# YOTSUBA_GNSS-receiver_MAX_ver_1_5.net
KiCad netlist of a schematic drawn in EAGLE
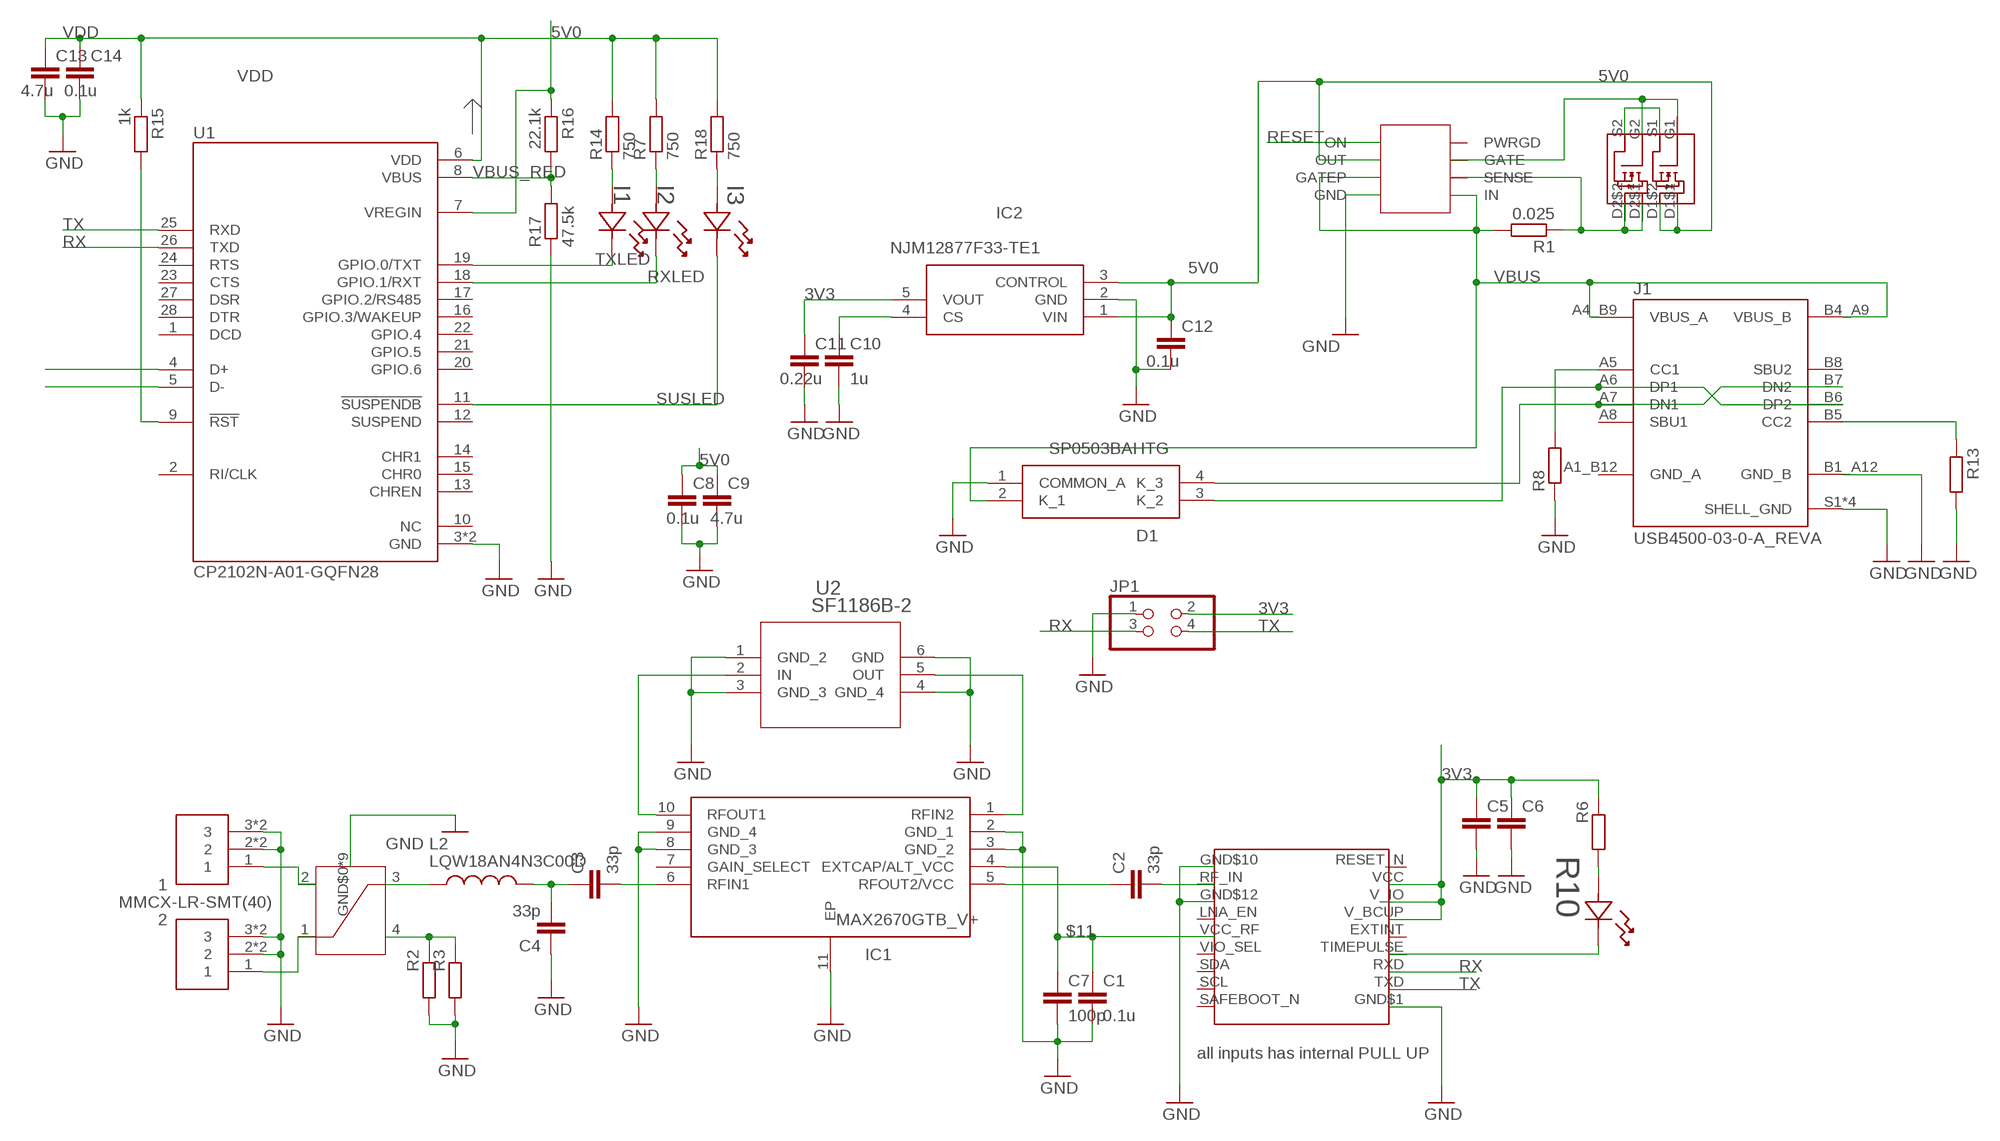
[diagram p0: schematic, sheet 1]

(export (version "E")
  (design (tool "Eeschema 10.0.6"))
  (components
    (comp (ref "1")
      (value "MMCX-LR-SMT(40)")
      (footprint "eagle-import:MMCX-LR-SMT(40)")
      (libsource (lib "eagle-import") (part "MMCX-LR-SMT(40)"))
    )
    (comp (ref "2")
      (value "MMCX-LR-SMT(40)")
      (footprint "eagle-import:MMCX-LR-SMT(40)")
      (libsource (lib "eagle-import") (part "MMCX-LR-SMT(40)"))
    )
    (comp (ref "C1")
      (value "0.1u")
      (footprint "eagle-import:C1608")
      (libsource (lib "eagle-import") (part "C-EUC1608"))
    )
    (comp (ref "C2")
      (value "33p")
      (footprint "eagle-import:C1608")
      (libsource (lib "eagle-import") (part "C-EUC1608"))
    )
    (comp (ref "C3")
      (value "33p")
      (footprint "eagle-import:C1608")
      (libsource (lib "eagle-import") (part "C-EUC1608"))
    )
    (comp (ref "C4")
      (value "33p")
      (footprint "eagle-import:C1608")
      (libsource (lib "eagle-import") (part "C-EUC1608"))
    )
    (comp (ref "C5")
      (value "C-EUC1608")
      (footprint "eagle-import:C1608")
      (libsource (lib "eagle-import") (part "C-EUC1608"))
    )
    (comp (ref "C6")
      (value "C-EUC1608")
      (footprint "eagle-import:C1608")
      (libsource (lib "eagle-import") (part "C-EUC1608"))
    )
    (comp (ref "C7")
      (value "100p")
      (footprint "eagle-import:C1608")
      (libsource (lib "eagle-import") (part "C-EUC1608"))
    )
    (comp (ref "C8")
      (value "0.1u")
      (footprint "eagle-import:C1608")
      (libsource (lib "eagle-import") (part "C-EUC1608"))
    )
    (comp (ref "C9")
      (value "4.7u")
      (footprint "eagle-import:C1608")
      (libsource (lib "eagle-import") (part "C-EUC1608"))
    )
    (comp (ref "C10")
      (value "1u")
      (footprint "eagle-import:C1608")
      (libsource (lib "eagle-import") (part "C-EUC1608"))
    )
    (comp (ref "C11")
      (value "0.22u")
      (footprint "eagle-import:C1608")
      (libsource (lib "eagle-import") (part "C-EUC1608"))
    )
    (comp (ref "C12")
      (value "0.1u")
      (footprint "eagle-import:C1608")
      (libsource (lib "eagle-import") (part "C-EUC1608"))
    )
    (comp (ref "C13")
      (value "4.7u")
      (footprint "eagle-import:C1608")
      (libsource (lib "eagle-import") (part "C-EUC1608"))
    )
    (comp (ref "C14")
      (value "0.1u")
      (footprint "eagle-import:C1608")
      (libsource (lib "eagle-import") (part "C-EUC1608"))
    )
    (comp (ref "D1")
      (value "SP0503BAHTG")
      (footprint "eagle-import:SP0503BAHTG")
      (fields (field (name "MOUSER_PART_NUMBER") "576-SP0503BAHTG"))
      (libsource (lib "eagle-import") (part "SP0503BAHTG"))
    )
    (comp (ref "I1")
      (value "SML-E12P8WT86")
      (footprint "eagle-import:LED_SMLD12_ROM")
      (fields (field (name "COPYRIGHT") "Copyright (C) 2023 Ultra Librarian. All rights reserved."))
      (libsource (lib "eagle-import") (part "SML-E12P8WT86"))
    )
    (comp (ref "I2")
      (value "SML-E12P8WT86")
      (footprint "eagle-import:LED_SMLD12_ROM")
      (fields (field (name "COPYRIGHT") "Copyright (C) 2023 Ultra Librarian. All rights reserved."))
      (libsource (lib "eagle-import") (part "SML-E12P8WT86"))
    )
    (comp (ref "I3")
      (value "SML-E12P8WT86")
      (footprint "eagle-import:LED_SMLD12_ROM")
      (fields (field (name "COPYRIGHT") "Copyright (C) 2023 Ultra Librarian. All rights reserved."))
      (libsource (lib "eagle-import") (part "SML-E12P8WT86"))
    )
    (comp (ref "IC1")
      (value "MAX2670GTB_V+")
      (footprint "eagle-import:SON50P300X300X80-11N")
      (fields
        (field (name "MANUFACTURER_PART_NUMBER") "MAX2670GTB/V+")
        (field (name "MOUSER_PART_NUMBER") "700-MAX2670GTB/V+")
      )
      (libsource (lib "eagle-import") (part "MAX2670GTB_V+"))
    )
    (comp (ref "IC2")
      (value "NJM12877F33-TE1")
      (footprint "eagle-import:SOT95P280X120-5N")
      (fields (field (name "MOUSER_PART_NUMBER") "513-NJM12877F33-TE1"))
      (libsource (lib "eagle-import") (part "NJM12877F33-TE1"))
    )
    (comp (ref "J1")
      (value "USB4500-03-0-A_REVA")
      (footprint "eagle-import:GCT_USB4500-03-0-A_REVA")
      (fields
        (field (name "DIGI-KEY_PART_NUMBER") "2073-USB4500-03-0-ATR-ND")
        (field (name "MF") "Global Connector Technology")
        (field (name "MP") "USB4500-03-0-A")
      )
      (libsource (lib "eagle-import") (part "USB4500-03-0-A_REVA"))
    )
    (comp (ref "JP1")
      (value "PINHD-2X2")
      (footprint "eagle-import:2X02")
      (libsource (lib "eagle-import") (part "PINHD-2X2"))
    )
    (comp (ref "L2")
      (value "LQW18AN4N3C00D")
      (footprint "eagle-import:INDC1608X100N")
      (fields (field (name "DIGIKEY_PART_NUMBER") "490-6896-2-ND") (field (name "MF") "Murata"))
      (libsource (lib "eagle-import") (part "LQW18AN4N3C00D"))
    )
    (comp (ref "R1")
      (value "0.025")
      (footprint "eagle-import:R0603")
      (libsource (lib "eagle-import") (part "R-EU_R0603"))
    )
    (comp (ref "R2")
      (value "R-EU_R0603")
      (footprint "eagle-import:R0603")
      (libsource (lib "eagle-import") (part "R-EU_R0603"))
    )
    (comp (ref "R3")
      (value "R-EU_R0603")
      (footprint "eagle-import:R0603")
      (libsource (lib "eagle-import") (part "R-EU_R0603"))
    )
    (comp (ref "R6")
      (value "R-EU_R0603")
      (footprint "eagle-import:R0603")
      (libsource (lib "eagle-import") (part "R-EU_R0603"))
    )
    (comp (ref "R7")
      (value "750")
      (footprint "eagle-import:R0603")
      (libsource (lib "eagle-import") (part "R-EU_R0603"))
    )
    (comp (ref "R8")
      (value "R-EU_R0603")
      (footprint "eagle-import:R0603")
      (libsource (lib "eagle-import") (part "R-EU_R0603"))
    )
    (comp (ref "R10")
      (value "SML-E12P8WT86")
      (footprint "eagle-import:LED_SMLD12_ROM")
      (fields (field (name "COPYRIGHT") "Copyright (C) 2023 Ultra Librarian. All rights reserved."))
      (libsource (lib "eagle-import") (part "SML-E12P8WT86"))
    )
    (comp (ref "R13")
      (value "R-EU_R0603")
      (footprint "eagle-import:R0603")
      (libsource (lib "eagle-import") (part "R-EU_R0603"))
    )
    (comp (ref "R14")
      (value "750")
      (footprint "eagle-import:R0603")
      (libsource (lib "eagle-import") (part "R-EU_R0603"))
    )
    (comp (ref "R15")
      (value "1k")
      (footprint "eagle-import:R0603")
      (libsource (lib "eagle-import") (part "R-EU_R0603"))
    )
    (comp (ref "R16")
      (value "22.1k")
      (footprint "eagle-import:R0603")
      (libsource (lib "eagle-import") (part "R-EU_R0603"))
    )
    (comp (ref "R17")
      (value "47.5k")
      (footprint "eagle-import:R0603")
      (libsource (lib "eagle-import") (part "R-EU_R0603"))
    )
    (comp (ref "R18")
      (value "750")
      (footprint "eagle-import:R0603")
      (libsource (lib "eagle-import") (part "R-EU_R0603"))
    )
    (comp (ref "U$1")
      (value "MAX_M10S")
      (footprint "eagle-import:MAX-M10S")
      (libsource (lib "eagle-import") (part "MAX_M10S"))
    )
    (comp (ref "U$3")
      (value "HC125.A")
      (footprint "eagle-import:HC125.A")
      (libsource (lib "eagle-import") (part "HC125.A"))
    )
    (comp (ref "U$7")
      (value "DMG6898LSD")
      (footprint "eagle-import:SOIC127P600X150-8N")
      (libsource (lib "eagle-import") (part "DMG6898LSD"))
    )
    (comp (ref "U$8")
      (value "LTC4361")
      (footprint "eagle-import:SOP65P280X100-8N")
      (libsource (lib "eagle-import") (part "LTC4361"))
    )
    (comp (ref "U1")
      (value "CP2102N-A01-GQFN28")
      (footprint "eagle-import:QFN50P500X500X80-29N")
      (fields (field (name "MF") "Silicon Labs"))
      (libsource (lib "eagle-import") (part "CP2102N-A01-GQFN28"))
    )
    (comp (ref "U2")
      (value "SF1186B-2")
      (footprint "eagle-import:SM3030_MUR")
      (fields (field (name "COPYRIGHT") "Copyright (C) 2023 Ultra Librarian. All rights reserved."))
      (libsource (lib "eagle-import") (part "SF1186B-2"))
    )
  )
  (nets
    (net (code "1") (name "/$11") (class "Default")
      (node (ref "C1") (pin "1") (pinfunction "1_1") (pintype "passive"))
      (node (ref "C7") (pin "1") (pinfunction "1_1") (pintype "passive"))
      (node (ref "IC1") (pin "4") (pinfunction "EXTCAP/ALT_VCC_4") (pintype "bidirectional"))
      (node (ref "U$1") (pin "VCC_RF") (pinfunction "VCC_RF_VCC_RF") (pintype "bidirectional"))
    )
    (net (code "2") (name "/3V3") (class "Default")
      (node (ref "C11") (pin "1") (pinfunction "1_1") (pintype "passive"))
      (node (ref "C5") (pin "1") (pinfunction "1_1") (pintype "passive"))
      (node (ref "C6") (pin "1") (pinfunction "1_1") (pintype "passive"))
      (node (ref "IC2") (pin "5") (pinfunction "VOUT_5") (pintype "bidirectional"))
      (node (ref "JP1") (pin "2") (pinfunction "2_2") (pintype "passive"))
      (node (ref "R6") (pin "2") (pinfunction "2_2") (pintype "passive"))
      (node (ref "U$1") (pin "VCC") (pinfunction "VCC_VCC") (pintype "bidirectional"))
      (node (ref "U$1") (pin "V_BCUP") (pinfunction "V_BCKP_V_BCUP") (pintype "bidirectional"))
      (node (ref "U$1") (pin "V_IO") (pinfunction "V_IO_V_IO") (pintype "bidirectional"))
    )
    (net (code "3") (name "/5V0") (class "Default")
      (node (ref "C12") (pin "1") (pinfunction "1_1") (pintype "passive"))
      (node (ref "C8") (pin "1") (pinfunction "1_1") (pintype "passive"))
      (node (ref "C9") (pin "1") (pinfunction "1_1") (pintype "passive"))
      (node (ref "IC2") (pin "1") (pinfunction "VIN_1") (pintype "bidirectional"))
      (node (ref "IC2") (pin "3") (pinfunction "CONTROL_3") (pintype "bidirectional"))
      (node (ref "R16") (pin "1") (pinfunction "1_1") (pintype "passive"))
      (node (ref "U$7") (pin "D1$1") (pinfunction "D1$1_D1$1") (pintype "bidirectional"))
      (node (ref "U$7") (pin "D1$2") (pinfunction "D1$2_D1$2") (pintype "bidirectional"))
      (node (ref "U$8") (pin "OUT") (pinfunction "OUT_OUT") (pintype "bidirectional"))
      (node (ref "U1") (pin "7") (pinfunction "VREGIN_7") (pintype "power_in"))
    )
    (net (code "4") (name "/D+") (class "Default")
      (node (ref "D1") (pin "3") (pinfunction "K_2_3") (pintype "bidirectional"))
      (node (ref "J1") (pin "A6") (pinfunction "DP1_A6") (pintype "bidirectional"))
      (node (ref "J1") (pin "B6") (pinfunction "DP2_B6") (pintype "bidirectional"))
      (node (ref "U1") (pin "4") (pinfunction "D+_4") (pintype "bidirectional"))
    )
    (net (code "5") (name "/D-") (class "Default")
      (node (ref "D1") (pin "4") (pinfunction "K_3_4") (pintype "bidirectional"))
      (node (ref "J1") (pin "A7") (pinfunction "DN1_A7") (pintype "bidirectional"))
      (node (ref "J1") (pin "B7") (pinfunction "DN2_B7") (pintype "bidirectional"))
      (node (ref "U1") (pin "5") (pinfunction "D-_5") (pintype "bidirectional"))
    )
    (net (code "6") (name "/GND_A") (class "Default")
      (node (ref "J1") (pin "A1_B12") (pinfunction "GND_A_A1_B12") (pintype "power_in"))
    )
    (net (code "7") (name "/RESET") (class "Default")
      (node (ref "U$8") (pin "ON") (pinfunction "ON_ON") (pintype "bidirectional"))
    )
    (net (code "8") (name "/RX") (class "Default")
      (node (ref "JP1") (pin "3") (pinfunction "3_3") (pintype "passive"))
      (node (ref "U$1") (pin "RXD") (pinfunction "RXD_RXD") (pintype "bidirectional"))
      (node (ref "U1") (pin "26") (pinfunction "TXD_26") (pintype "output"))
    )
    (net (code "9") (name "/RXLED") (class "Default")
      (node (ref "I2") (pin "1") (pinfunction "1_1") (pintype "passive"))
      (node (ref "U1") (pin "18") (pinfunction "GPIO.1/RXT_18") (pintype "bidirectional"))
    )
    (net (code "10") (name "/SUSLED") (class "Default")
      (node (ref "I3") (pin "1") (pinfunction "1_1") (pintype "passive"))
      (node (ref "U1") (pin "11") (pinfunction "~{SUSPENDB}_11") (pintype "output"))
    )
    (net (code "11") (name "/TX") (class "Default")
      (node (ref "JP1") (pin "4") (pinfunction "4_4") (pintype "passive"))
      (node (ref "U$1") (pin "TXD") (pinfunction "TXD_TXD") (pintype "bidirectional"))
      (node (ref "U1") (pin "25") (pinfunction "RXD_25") (pintype "input"))
    )
    (net (code "12") (name "/TXLED") (class "Default")
      (node (ref "I1") (pin "1") (pinfunction "1_1") (pintype "passive"))
      (node (ref "U1") (pin "19") (pinfunction "GPIO.0/TXT_19") (pintype "bidirectional"))
    )
    (net (code "13") (name "/VBUS") (class "Default")
      (node (ref "D1") (pin "2") (pinfunction "K_1_2") (pintype "bidirectional"))
      (node (ref "J1") (pin "A4_B9") (pinfunction "VBUS_A_A4_B9") (pintype "power_in"))
      (node (ref "J1") (pin "B4_A9") (pinfunction "VBUS_B_B4_A9") (pintype "power_in"))
      (node (ref "R1") (pin "2") (pinfunction "2_2") (pintype "passive"))
      (node (ref "U$8") (pin "GATEP") (pinfunction "GATEP_GATEP") (pintype "bidirectional"))
      (node (ref "U$8") (pin "IN") (pinfunction "IN_IN") (pintype "bidirectional"))
    )
    (net (code "14") (name "/VBUS_RED") (class "Default")
      (node (ref "R16") (pin "2") (pinfunction "2_2") (pintype "passive"))
      (node (ref "R17") (pin "2") (pinfunction "2_2") (pintype "passive"))
      (node (ref "U1") (pin "8") (pinfunction "VBUS_8") (pintype "power_in"))
    )
    (net (code "15") (name "/VDD") (class "Default")
      (node (ref "C13") (pin "1") (pinfunction "1_1") (pintype "passive"))
      (node (ref "C14") (pin "1") (pinfunction "1_1") (pintype "passive"))
      (node (ref "R14") (pin "2") (pinfunction "2_2") (pintype "passive"))
      (node (ref "R15") (pin "1") (pinfunction "1_1") (pintype "passive"))
      (node (ref "R18") (pin "2") (pinfunction "2_2") (pintype "passive"))
      (node (ref "R7") (pin "2") (pinfunction "2_2") (pintype "passive"))
      (node (ref "U1") (pin "6") (pinfunction "VDD_6") (pintype "power_in"))
    )
    (net (code "16") (name "GND") (class "Default")
      (node (ref "1") (pin "2") (pinfunction "2_2") (pintype "bidirectional"))
      (node (ref "1") (pin "3") (pinfunction "3_3") (pintype "bidirectional"))
      (node (ref "1") (pin "4") (pinfunction "2_4") (pintype "bidirectional"))
      (node (ref "1") (pin "5") (pinfunction "3_5") (pintype "bidirectional"))
      (node (ref "2") (pin "2") (pinfunction "2_2") (pintype "bidirectional"))
      (node (ref "2") (pin "3") (pinfunction "3_3") (pintype "bidirectional"))
      (node (ref "2") (pin "4") (pinfunction "2_4") (pintype "bidirectional"))
      (node (ref "2") (pin "5") (pinfunction "3_5") (pintype "bidirectional"))
      (node (ref "C1") (pin "2") (pinfunction "2_2") (pintype "passive"))
      (node (ref "C10") (pin "2") (pinfunction "2_2") (pintype "passive"))
      (node (ref "C11") (pin "2") (pinfunction "2_2") (pintype "passive"))
      (node (ref "C12") (pin "2") (pinfunction "2_2") (pintype "passive"))
      (node (ref "C13") (pin "2") (pinfunction "2_2") (pintype "passive"))
      (node (ref "C14") (pin "2") (pinfunction "2_2") (pintype "passive"))
      (node (ref "C4") (pin "1") (pinfunction "1_1") (pintype "passive"))
      (node (ref "C5") (pin "2") (pinfunction "2_2") (pintype "passive"))
      (node (ref "C6") (pin "2") (pinfunction "2_2") (pintype "passive"))
      (node (ref "C7") (pin "2") (pinfunction "2_2") (pintype "passive"))
      (node (ref "C8") (pin "2") (pinfunction "2_2") (pintype "passive"))
      (node (ref "C9") (pin "2") (pinfunction "2_2") (pintype "passive"))
      (node (ref "D1") (pin "1") (pinfunction "COMMON_A_1") (pintype "bidirectional"))
      (node (ref "IC1") (pin "11") (pinfunction "EP_11") (pintype "bidirectional"))
      (node (ref "IC1") (pin "2") (pinfunction "GND_1_2") (pintype "bidirectional"))
      (node (ref "IC1") (pin "3") (pinfunction "GND_2_3") (pintype "bidirectional"))
      (node (ref "IC1") (pin "8") (pinfunction "GND_3_8") (pintype "bidirectional"))
      (node (ref "IC1") (pin "9") (pinfunction "GND_4_9") (pintype "bidirectional"))
      (node (ref "IC2") (pin "2") (pinfunction "GND_2") (pintype "bidirectional"))
      (node (ref "J1") (pin "B1_A12") (pinfunction "GND_B_B1_A12") (pintype "power_in"))
      (node (ref "J1") (pin "S1") (pinfunction "SHELL_GND_S1") (pintype "power_in"))
      (node (ref "J1") (pin "S2") (pinfunction "SHELL_GND_S2") (pintype "power_in"))
      (node (ref "J1") (pin "S3") (pinfunction "SHELL_GND_S3") (pintype "power_in"))
      (node (ref "J1") (pin "S4") (pinfunction "SHELL_GND_S4") (pintype "power_in"))
      (node (ref "JP1") (pin "1") (pinfunction "1_1") (pintype "passive"))
      (node (ref "R13") (pin "2") (pinfunction "2_2") (pintype "passive"))
      (node (ref "R17") (pin "1") (pinfunction "1_1") (pintype "passive"))
      (node (ref "R2") (pin "1") (pinfunction "1_1") (pintype "passive"))
      (node (ref "R3") (pin "1") (pinfunction "1_1") (pintype "passive"))
      (node (ref "R8") (pin "1") (pinfunction "1_1") (pintype "passive"))
      (node (ref "U$1") (pin "GND$1") (pinfunction "GND$1_GND$1") (pintype "bidirectional"))
      (node (ref "U$1") (pin "GND$10") (pinfunction "GND$10_GND$10") (pintype "bidirectional"))
      (node (ref "U$1") (pin "GND$12") (pinfunction "GND$12_GND$12") (pintype "bidirectional"))
      (node (ref "U$3") (pin "GND$0") (pinfunction "GND_GND$0") (pintype "bidirectional"))
      (node (ref "U$3") (pin "GND$1") (pinfunction "GND_GND$1") (pintype "bidirectional"))
      (node (ref "U$3") (pin "GND$2") (pinfunction "GND_GND$2") (pintype "bidirectional"))
      (node (ref "U$3") (pin "GND$3") (pinfunction "GND_GND$3") (pintype "bidirectional"))
      (node (ref "U$3") (pin "GND$4") (pinfunction "GND_GND$4") (pintype "bidirectional"))
      (node (ref "U$3") (pin "GND$5") (pinfunction "GND_GND$5") (pintype "bidirectional"))
      (node (ref "U$3") (pin "GND$6") (pinfunction "GND_GND$6") (pintype "bidirectional"))
      (node (ref "U$3") (pin "GND$7") (pinfunction "GND_GND$7") (pintype "bidirectional"))
      (node (ref "U$3") (pin "GND$8") (pinfunction "GND_GND$8") (pintype "bidirectional"))
      (node (ref "U$8") (pin "GND") (pinfunction "GND_GND") (pintype "bidirectional"))
      (node (ref "U1") (pin "29") (pinfunction "GND_29") (pintype "power_in"))
      (node (ref "U1") (pin "3") (pinfunction "GND_3") (pintype "power_in"))
      (node (ref "U2") (pin "1") (pinfunction "GND_2_1") (pintype "passive"))
      (node (ref "U2") (pin "3") (pinfunction "GND_3_3") (pintype "passive"))
      (node (ref "U2") (pin "4") (pinfunction "GND_4_4") (pintype "passive"))
      (node (ref "U2") (pin "6") (pinfunction "GND_6") (pintype "passive"))
    )
    (net (code "17") (name "Net-(1-Pad1)") (class "Default")
      (node (ref "1") (pin "1") (pinfunction "1_1") (pintype "bidirectional"))
      (node (ref "U$3") (pin "2") (pinfunction "2_2") (pintype "bidirectional"))
    )
    (net (code "18") (name "Net-(2-Pad1)") (class "Default")
      (node (ref "2") (pin "1") (pinfunction "1_1") (pintype "bidirectional"))
      (node (ref "U$3") (pin "1") (pinfunction "1_1") (pintype "bidirectional"))
    )
    (net (code "19") (name "Net-(C2-Pad2)") (class "Default")
      (node (ref "C2") (pin "2") (pinfunction "2_2") (pintype "passive"))
      (node (ref "U$1") (pin "RF_IN") (pinfunction "RF_IN_RF_IN") (pintype "bidirectional"))
    )
    (net (code "20") (name "Net-(C3-Pad1)") (class "Default")
      (node (ref "C3") (pin "1") (pinfunction "1_1") (pintype "passive"))
      (node (ref "C4") (pin "2") (pinfunction "2_2") (pintype "passive"))
      (node (ref "L2") (pin "2") (pinfunction "2_2") (pintype "passive"))
    )
    (net (code "21") (name "Net-(I1-Pad2)") (class "Default")
      (node (ref "I1") (pin "2") (pinfunction "2_2") (pintype "passive"))
      (node (ref "R14") (pin "1") (pinfunction "1_1") (pintype "passive"))
    )
    (net (code "22") (name "Net-(I2-Pad2)") (class "Default")
      (node (ref "I2") (pin "2") (pinfunction "2_2") (pintype "passive"))
      (node (ref "R7") (pin "1") (pinfunction "1_1") (pintype "passive"))
    )
    (net (code "23") (name "Net-(I3-Pad2)") (class "Default")
      (node (ref "I3") (pin "2") (pinfunction "2_2") (pintype "passive"))
      (node (ref "R18") (pin "1") (pinfunction "1_1") (pintype "passive"))
    )
    (net (code "24") (name "Net-(IC1-RFIN1)") (class "Default")
      (node (ref "C3") (pin "2") (pinfunction "2_2") (pintype "passive"))
      (node (ref "IC1") (pin "6") (pinfunction "RFIN1_6") (pintype "bidirectional"))
    )
    (net (code "25") (name "Net-(IC1-RFIN2)") (class "Default")
      (node (ref "IC1") (pin "1") (pinfunction "RFIN2_1") (pintype "bidirectional"))
      (node (ref "U2") (pin "5") (pinfunction "OUT_5") (pintype "output"))
    )
    (net (code "26") (name "Net-(IC1-RFOUT1)") (class "Default")
      (node (ref "IC1") (pin "10") (pinfunction "RFOUT1_10") (pintype "bidirectional"))
      (node (ref "U2") (pin "2") (pinfunction "IN_2") (pintype "input"))
    )
    (net (code "27") (name "Net-(IC1-RFOUT2{slash}VCC)") (class "Default")
      (node (ref "C2") (pin "1") (pinfunction "1_1") (pintype "passive"))
      (node (ref "IC1") (pin "5") (pinfunction "RFOUT2/VCC_5") (pintype "bidirectional"))
    )
    (net (code "28") (name "Net-(IC2-CS)") (class "Default")
      (node (ref "C10") (pin "1") (pinfunction "1_1") (pintype "passive"))
      (node (ref "IC2") (pin "4") (pinfunction "CS_4") (pintype "bidirectional"))
    )
    (net (code "29") (name "Net-(J1-CC1)") (class "Default")
      (node (ref "J1") (pin "A5") (pinfunction "CC1_A5") (pintype "bidirectional"))
      (node (ref "R8") (pin "2") (pinfunction "2_2") (pintype "passive"))
    )
    (net (code "30") (name "Net-(J1-CC2)") (class "Default")
      (node (ref "J1") (pin "B5") (pinfunction "CC2_B5") (pintype "bidirectional"))
      (node (ref "R13") (pin "1") (pinfunction "1_1") (pintype "passive"))
    )
    (net (code "31") (name "Net-(L2-Pad1)") (class "Default")
      (node (ref "L2") (pin "1") (pinfunction "1_1") (pintype "passive"))
      (node (ref "U$3") (pin "3") (pinfunction "3_3") (pintype "bidirectional"))
    )
    (net (code "32") (name "Net-(R1-Pad1)") (class "Default")
      (node (ref "R1") (pin "1") (pinfunction "1_1") (pintype "passive"))
      (node (ref "U$7") (pin "D2$1") (pinfunction "D2$1_D2$1") (pintype "bidirectional"))
      (node (ref "U$7") (pin "D2$2") (pinfunction "D2$2_D2$2") (pintype "bidirectional"))
      (node (ref "U$8") (pin "SENSE") (pinfunction "SENSE_SENSE") (pintype "bidirectional"))
    )
    (net (code "33") (name "Net-(R2-Pad2)") (class "Default")
      (node (ref "R2") (pin "2") (pinfunction "2_2") (pintype "passive"))
      (node (ref "R3") (pin "2") (pinfunction "2_2") (pintype "passive"))
      (node (ref "U$3") (pin "4") (pinfunction "4_4") (pintype "bidirectional"))
    )
    (net (code "34") (name "Net-(R10-Pad1)") (class "Default")
      (node (ref "R10") (pin "1") (pinfunction "1_1") (pintype "passive"))
      (node (ref "U$1") (pin "TIMEPULSE") (pinfunction "TIMEPULSE_TIMEPULSE") (pintype "bidirectional"))
    )
    (net (code "35") (name "Net-(R10-Pad2)") (class "Default")
      (node (ref "R10") (pin "2") (pinfunction "2_2") (pintype "passive"))
      (node (ref "R6") (pin "1") (pinfunction "1_1") (pintype "passive"))
    )
    (net (code "36") (name "Net-(U$7-PadG1)") (class "Default")
      (node (ref "U$7") (pin "G1") (pinfunction "G1_G1") (pintype "bidirectional"))
      (node (ref "U$7") (pin "G2") (pinfunction "G2_G2") (pintype "bidirectional"))
      (node (ref "U$8") (pin "GATE") (pinfunction "GATE_GATE") (pintype "bidirectional"))
    )
    (net (code "37") (name "Net-(U$7-PadS1)") (class "Default")
      (node (ref "U$7") (pin "S1") (pinfunction "S1_S1") (pintype "bidirectional"))
      (node (ref "U$7") (pin "S2") (pinfunction "S2_S2") (pintype "bidirectional"))
    )
    (net (code "38") (name "Net-(U1-~{RST})") (class "Default")
      (node (ref "R15") (pin "2") (pinfunction "2_2") (pintype "passive"))
      (node (ref "U1") (pin "9") (pinfunction "~{RST}_9") (pintype "input"))
    )
    (net (code "39") (name "unconnected-(IC1-GAIN_SELECT-Pad7)") (class "Default")
      (node (ref "IC1") (pin "7") (pinfunction "GAIN_SELECT_7") (pintype "bidirectional"))
    )
    (net (code "40") (name "unconnected-(J1-SBU1-PadA8)") (class "Default")
      (node (ref "J1") (pin "A8") (pinfunction "SBU1_A8") (pintype "bidirectional"))
    )
    (net (code "41") (name "unconnected-(J1-SBU2-PadB8)") (class "Default")
      (node (ref "J1") (pin "B8") (pinfunction "SBU2_B8") (pintype "bidirectional"))
    )
    (net (code "42") (name "unconnected-(U$1-PadEXTINT)") (class "Default")
      (node (ref "U$1") (pin "EXTINT") (pinfunction "EXTINT_EXTINT") (pintype "bidirectional"))
    )
    (net (code "43") (name "unconnected-(U$1-PadLNA_EN)") (class "Default")
      (node (ref "U$1") (pin "LNA_EN") (pinfunction "LNA_EN_LNA_EN") (pintype "bidirectional"))
    )
    (net (code "44") (name "unconnected-(U$1-PadRESET_N)") (class "Default")
      (node (ref "U$1") (pin "RESET_N") (pinfunction "RESET_N_RESET_N") (pintype "bidirectional"))
    )
    (net (code "45") (name "unconnected-(U$1-PadSAFEBOOT_N)") (class "Default")
      (node (ref "U$1") (pin "SAFEBOOT_N") (pinfunction "SAFEBOOT_N_SAFEBOOT_N") (pintype "bidirectional"))
    )
    (net (code "46") (name "unconnected-(U$1-PadSCL)") (class "Default")
      (node (ref "U$1") (pin "SCL") (pinfunction "SCL_SCL") (pintype "bidirectional"))
    )
    (net (code "47") (name "unconnected-(U$1-PadSDA)") (class "Default")
      (node (ref "U$1") (pin "SDA") (pinfunction "SDA_SDA") (pintype "bidirectional"))
    )
    (net (code "48") (name "unconnected-(U$1-PadVIO_SEL)") (class "Default")
      (node (ref "U$1") (pin "VIO_SEL") (pinfunction "VIO_SEL_VIO_SEL") (pintype "bidirectional"))
    )
    (net (code "49") (name "unconnected-(U$8-PadPWRGD)") (class "Default")
      (node (ref "U$8") (pin "PWRGD") (pinfunction "PWRGD_PWRGD") (pintype "bidirectional"))
    )
    (net (code "50") (name "unconnected-(U1-CHR0-Pad15)") (class "Default")
      (node (ref "U1") (pin "15") (pinfunction "CHR0_15") (pintype "output"))
    )
    (net (code "51") (name "unconnected-(U1-CHR1-Pad14)") (class "Default")
      (node (ref "U1") (pin "14") (pinfunction "CHR1_14") (pintype "output"))
    )
    (net (code "52") (name "unconnected-(U1-CHREN-Pad13)") (class "Default")
      (node (ref "U1") (pin "13") (pinfunction "CHREN_13") (pintype "output"))
    )
    (net (code "53") (name "unconnected-(U1-CTS-Pad23)") (class "Default")
      (node (ref "U1") (pin "23") (pinfunction "CTS_23") (pintype "input"))
    )
    (net (code "54") (name "unconnected-(U1-DCD-Pad1)") (class "Default")
      (node (ref "U1") (pin "1") (pinfunction "DCD_1") (pintype "input"))
    )
    (net (code "55") (name "unconnected-(U1-DSR-Pad27)") (class "Default")
      (node (ref "U1") (pin "27") (pinfunction "DSR_27") (pintype "input"))
    )
    (net (code "56") (name "unconnected-(U1-DTR-Pad28)") (class "Default")
      (node (ref "U1") (pin "28") (pinfunction "DTR_28") (pintype "output"))
    )
    (net (code "57") (name "unconnected-(U1-GPIO.2{slash}RS485-Pad17)") (class "Default")
      (node (ref "U1") (pin "17") (pinfunction "GPIO.2/RS485_17") (pintype "bidirectional"))
    )
    (net (code "58") (name "unconnected-(U1-GPIO.3{slash}WAKEUP-Pad16)") (class "Default")
      (node (ref "U1") (pin "16") (pinfunction "GPIO.3/WAKEUP_16") (pintype "bidirectional"))
    )
    (net (code "59") (name "unconnected-(U1-GPIO.4-Pad22)") (class "Default")
      (node (ref "U1") (pin "22") (pinfunction "GPIO.4_22") (pintype "bidirectional"))
    )
    (net (code "60") (name "unconnected-(U1-GPIO.5-Pad21)") (class "Default")
      (node (ref "U1") (pin "21") (pinfunction "GPIO.5_21") (pintype "bidirectional"))
    )
    (net (code "61") (name "unconnected-(U1-GPIO.6-Pad20)") (class "Default")
      (node (ref "U1") (pin "20") (pinfunction "GPIO.6_20") (pintype "bidirectional"))
    )
    (net (code "62") (name "unconnected-(U1-NC-Pad10)") (class "Default")
      (node (ref "U1") (pin "10") (pinfunction "NC_10") (pintype "no_connect"))
    )
    (net (code "63") (name "unconnected-(U1-RI{slash}CLK-Pad2)") (class "Default")
      (node (ref "U1") (pin "2") (pinfunction "RI/CLK_2") (pintype "bidirectional"))
    )
    (net (code "64") (name "unconnected-(U1-RTS-Pad24)") (class "Default")
      (node (ref "U1") (pin "24") (pinfunction "RTS_24") (pintype "output"))
    )
    (net (code "65") (name "unconnected-(U1-SUSPEND-Pad12)") (class "Default")
      (node (ref "U1") (pin "12") (pinfunction "SUSPEND_12") (pintype "output"))
    )
  )
)
